# OPAMP_TESTER_3.net
KiCad netlist of a schematic drawn in Altium Designer
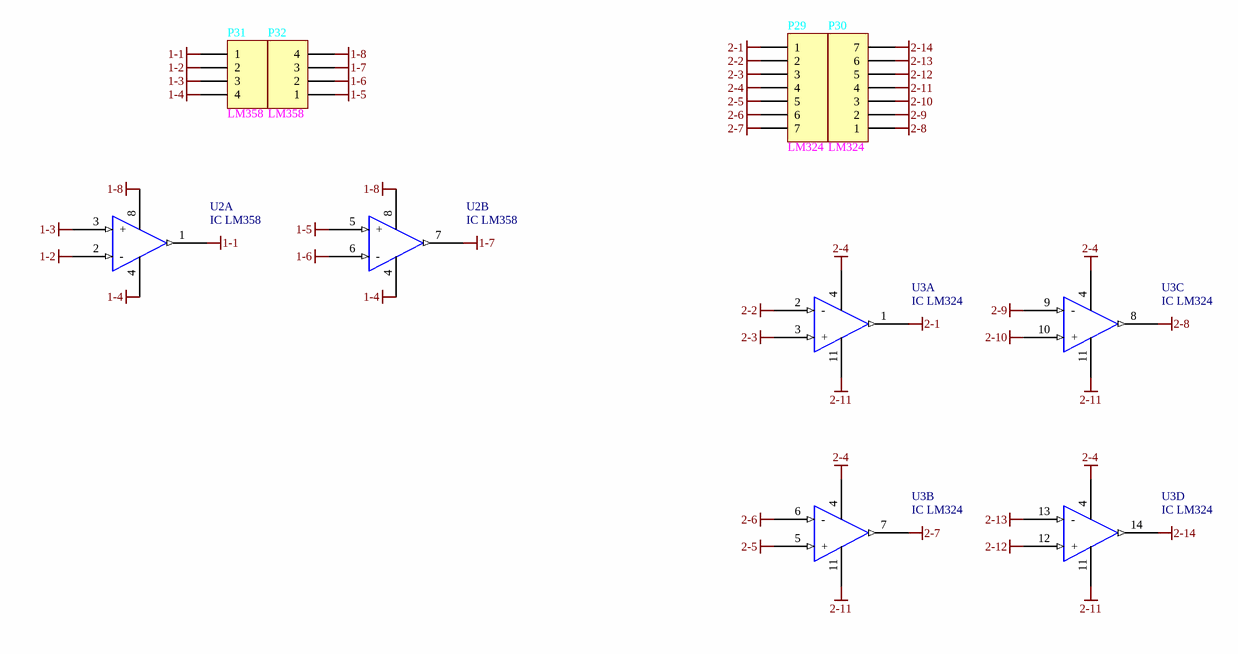
[diagram p0: OPAMP_TESTER_3.SchDoc]

(export (version "E")
  (design (tool "Eeschema 10.0.6"))
  (components
    (comp (ref "P29")
      (value "LM324")
      (footprint "CON HDR 2.54FM 7")
      (description "Header, 7-Pin")
      (fields (field (name "PUBLISHER") "Altium Limited"))
      (libsource (lib "Parlarlib_30") (part "CONNECTOR 7"))
    )
    (comp (ref "P30")
      (value "LM324")
      (footprint "CON HDR 2.54FM 7")
      (description "Header, 7-Pin")
      (fields (field (name "PUBLISHER") "Altium Limited"))
      (libsource (lib "") (part "CONNECTOR 7_1"))
    )
    (comp (ref "P31")
      (value "LM358")
      (footprint "CON HDR 2.54FM 4")
      (description "Header, 4-Pin")
      (fields (field (name "PUBLISHER") "Altium Limited"))
      (libsource (lib "") (part "CONNECTOR 4_1"))
    )
    (comp (ref "P32")
      (value "LM358")
      (footprint "CON HDR 2.54FM 4")
      (description "Header, 4-Pin")
      (fields (field (name "PUBLISHER") "Altium Limited"))
      (libsource (lib "Parlarlib_30") (part "CONNECTOR 4"))
    )
    (comp (ref "U2")
      (value "IC LM358")
      (footprint "SMD IC SOP8")
      (libsource (lib "Parlarlib_30") (part "IC LM358"))
    )
    (comp (ref "U3")
      (value "IC LM324")
      (footprint "SMD IC SOP14")
      (libsource (lib "Parlarlib_30") (part "IC LM324"))
    )
  )
  (nets
    (net (code "1") (name "1-1") (class "Default")
      (node (ref "P31") (pin "1") (pinfunction "1_1") (pintype "passive"))
      (node (ref "U2") (pin "1") (pinfunction "OUT1_1") (pintype "output"))
    )
    (net (code "2") (name "1-2") (class "Default")
      (node (ref "P31") (pin "2") (pinfunction "2_2") (pintype "passive"))
      (node (ref "U2") (pin "2") (pinfunction "-_2") (pintype "input"))
    )
    (net (code "3") (name "1-3") (class "Default")
      (node (ref "P31") (pin "3") (pinfunction "3_3") (pintype "passive"))
      (node (ref "U2") (pin "3") (pinfunction "+_3") (pintype "input"))
    )
    (net (code "4") (name "1-4") (class "Default")
      (node (ref "P31") (pin "4") (pinfunction "4_4") (pintype "passive"))
      (node (ref "U2") (pin "4") (pinfunction "GND_4") (pintype "passive"))
    )
    (net (code "5") (name "1-5") (class "Default")
      (node (ref "P32") (pin "1") (pinfunction "1_1") (pintype "passive"))
      (node (ref "U2") (pin "5") (pinfunction "+_5") (pintype "input"))
    )
    (net (code "6") (name "1-6") (class "Default")
      (node (ref "P32") (pin "2") (pinfunction "2_2") (pintype "passive"))
      (node (ref "U2") (pin "6") (pinfunction "-_6") (pintype "input"))
    )
    (net (code "7") (name "1-7") (class "Default")
      (node (ref "P32") (pin "3") (pinfunction "3_3") (pintype "passive"))
      (node (ref "U2") (pin "7") (pinfunction "OUT1_7") (pintype "output"))
    )
    (net (code "8") (name "1-8") (class "Default")
      (node (ref "P32") (pin "4") (pinfunction "4_4") (pintype "passive"))
      (node (ref "U2") (pin "8") (pinfunction "VCC_8") (pintype "passive"))
    )
    (net (code "9") (name "2-1") (class "Default")
      (node (ref "P29") (pin "1") (pinfunction "1_1") (pintype "passive"))
      (node (ref "U3") (pin "1") (pinfunction "OUT1_1") (pintype "output"))
    )
    (net (code "10") (name "2-2") (class "Default")
      (node (ref "P29") (pin "2") (pinfunction "2_2") (pintype "passive"))
      (node (ref "U3") (pin "2") (pinfunction "-_2") (pintype "input"))
    )
    (net (code "11") (name "2-3") (class "Default")
      (node (ref "P29") (pin "3") (pinfunction "3_3") (pintype "passive"))
      (node (ref "U3") (pin "3") (pinfunction "+_3") (pintype "input"))
    )
    (net (code "12") (name "2-4") (class "Default")
      (node (ref "P29") (pin "4") (pinfunction "4_4") (pintype "passive"))
      (node (ref "U3") (pin "4") (pinfunction "VCC_4") (pintype "passive"))
    )
    (net (code "13") (name "2-5") (class "Default")
      (node (ref "P29") (pin "5") (pinfunction "5_5") (pintype "passive"))
      (node (ref "U3") (pin "5") (pinfunction "+_5") (pintype "input"))
    )
    (net (code "14") (name "2-6") (class "Default")
      (node (ref "P29") (pin "6") (pinfunction "6_6") (pintype "passive"))
      (node (ref "U3") (pin "6") (pinfunction "-_6") (pintype "input"))
    )
    (net (code "15") (name "2-7") (class "Default")
      (node (ref "P29") (pin "7") (pinfunction "7_7") (pintype "passive"))
      (node (ref "U3") (pin "7") (pinfunction "OUT1_7") (pintype "output"))
    )
    (net (code "16") (name "2-8") (class "Default")
      (node (ref "P30") (pin "1") (pinfunction "1_1") (pintype "passive"))
      (node (ref "U3") (pin "8") (pinfunction "OUT1_8") (pintype "output"))
    )
    (net (code "17") (name "2-9") (class "Default")
      (node (ref "P30") (pin "2") (pinfunction "2_2") (pintype "passive"))
      (node (ref "U3") (pin "9") (pinfunction "-_9") (pintype "input"))
    )
    (net (code "18") (name "2-10") (class "Default")
      (node (ref "P30") (pin "3") (pinfunction "3_3") (pintype "passive"))
      (node (ref "U3") (pin "10") (pinfunction "+_10") (pintype "input"))
    )
    (net (code "19") (name "2-11") (class "Default")
      (node (ref "P30") (pin "4") (pinfunction "4_4") (pintype "passive"))
      (node (ref "U3") (pin "11") (pinfunction "GND_11") (pintype "passive"))
    )
    (net (code "20") (name "2-12") (class "Default")
      (node (ref "P30") (pin "5") (pinfunction "5_5") (pintype "passive"))
      (node (ref "U3") (pin "12") (pinfunction "+_12") (pintype "input"))
    )
    (net (code "21") (name "2-13") (class "Default")
      (node (ref "P30") (pin "6") (pinfunction "6_6") (pintype "passive"))
      (node (ref "U3") (pin "13") (pinfunction "-_13") (pintype "input"))
    )
    (net (code "22") (name "2-14") (class "Default")
      (node (ref "P30") (pin "7") (pinfunction "7_7") (pintype "passive"))
      (node (ref "U3") (pin "14") (pinfunction "OUT1_14") (pintype "output"))
    )
  )
)
